# ewal.net
KiCad netlist of a schematic drawn in EAGLE
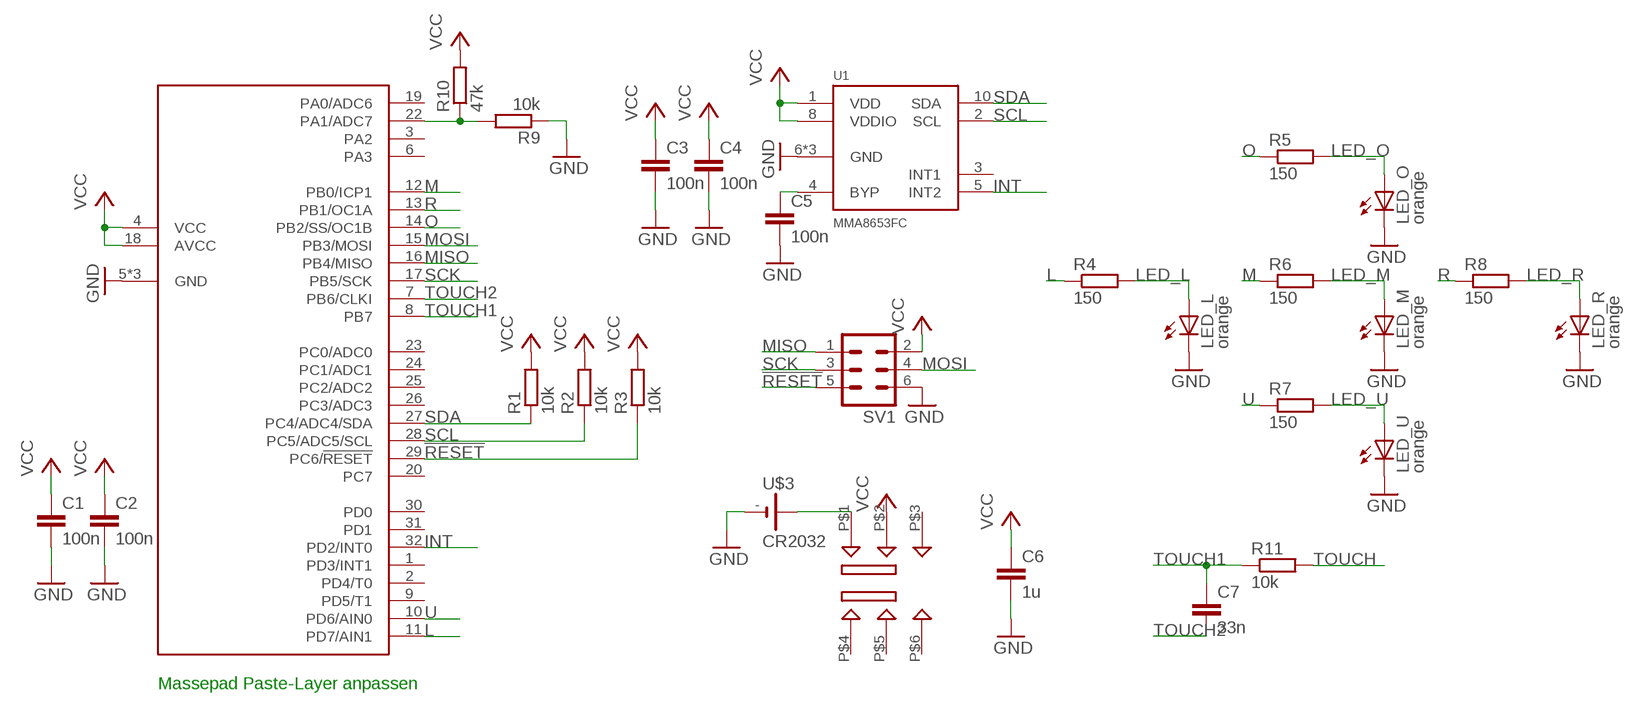
[diagram p0: schematic, sheet 1]

(export (version "E")
  (design (tool "Eeschema 10.0.6"))
  (components
    (comp (ref "C1")
      (value "100n")
      (footprint "eagle-import:C0603")
      (libsource (lib "eagle-import") (part "C-EUC0603"))
    )
    (comp (ref "C2")
      (value "100n")
      (footprint "eagle-import:C0603")
      (libsource (lib "eagle-import") (part "C-EUC0603"))
    )
    (comp (ref "C3")
      (value "100n")
      (footprint "eagle-import:C0603")
      (libsource (lib "eagle-import") (part "C-EUC0603"))
    )
    (comp (ref "C4")
      (value "100n")
      (footprint "eagle-import:C0603")
      (libsource (lib "eagle-import") (part "C-EUC0603"))
    )
    (comp (ref "C5")
      (value "100n")
      (footprint "eagle-import:C0603")
      (libsource (lib "eagle-import") (part "C-EUC0603"))
    )
    (comp (ref "C6")
      (value "1u")
      (footprint "eagle-import:C0805")
      (libsource (lib "eagle-import") (part "C-EUC0805"))
    )
    (comp (ref "C7")
      (value "33n")
      (footprint "eagle-import:C0603")
      (libsource (lib "eagle-import") (part "C-EUC0603"))
    )
    (comp (ref "LED_L")
      (value "orange")
      (footprint "eagle-import:CHIP-LED0603")
      (libsource (lib "eagle-import") (part "LEDCHIP-LED0603"))
    )
    (comp (ref "LED_M")
      (value "orange")
      (footprint "eagle-import:CHIP-LED0603")
      (libsource (lib "eagle-import") (part "LEDCHIP-LED0603"))
    )
    (comp (ref "LED_O")
      (value "orange")
      (footprint "eagle-import:CHIP-LED0603")
      (libsource (lib "eagle-import") (part "LEDCHIP-LED0603"))
    )
    (comp (ref "LED_R")
      (value "orange")
      (footprint "eagle-import:CHIP-LED0603")
      (libsource (lib "eagle-import") (part "LEDCHIP-LED0603"))
    )
    (comp (ref "LED_U")
      (value "orange")
      (footprint "eagle-import:CHIP-LED0603")
      (libsource (lib "eagle-import") (part "LEDCHIP-LED0603"))
    )
    (comp (ref "R1")
      (value "10k")
      (footprint "eagle-import:R0603")
      (libsource (lib "eagle-import") (part "R-EU_R0603"))
    )
    (comp (ref "R2")
      (value "10k")
      (footprint "eagle-import:R0603")
      (libsource (lib "eagle-import") (part "R-EU_R0603"))
    )
    (comp (ref "R3")
      (value "10k")
      (footprint "eagle-import:R0603")
      (libsource (lib "eagle-import") (part "R-EU_R0603"))
    )
    (comp (ref "R4")
      (value "150")
      (footprint "eagle-import:R0603")
      (libsource (lib "eagle-import") (part "R-EU_R0603"))
    )
    (comp (ref "R5")
      (value "150")
      (footprint "eagle-import:R0603")
      (libsource (lib "eagle-import") (part "R-EU_R0603"))
    )
    (comp (ref "R6")
      (value "150")
      (footprint "eagle-import:R0603")
      (libsource (lib "eagle-import") (part "R-EU_R0603"))
    )
    (comp (ref "R7")
      (value "150")
      (footprint "eagle-import:R0603")
      (libsource (lib "eagle-import") (part "R-EU_R0603"))
    )
    (comp (ref "R8")
      (value "150")
      (footprint "eagle-import:R0603")
      (libsource (lib "eagle-import") (part "R-EU_R0603"))
    )
    (comp (ref "R9")
      (value "10k")
      (footprint "eagle-import:R0603")
      (libsource (lib "eagle-import") (part "R-EU_R0603"))
    )
    (comp (ref "R10")
      (value "47k")
      (footprint "eagle-import:R0603")
      (libsource (lib "eagle-import") (part "R-EU_R0603"))
    )
    (comp (ref "R11")
      (value "10k")
      (footprint "eagle-import:R0603")
      (libsource (lib "eagle-import") (part "R-EU_R0603"))
    )
    (comp (ref "SV1")
      (value "MA03-2")
      (footprint "eagle-import:MA03-2")
      (libsource (lib "eagle-import") (part "MA03-2"))
    )
    (comp (ref "U$3")
      (value "CR2032")
      (footprint "eagle-import:BK-912")
      (libsource (lib "eagle-import") (part "CR2032"))
    )
    (comp (ref "U$4")
      (value "JS202011SCQN")
      (footprint "eagle-import:JS202011SCQN")
      (libsource (lib "eagle-import") (part "JS202011SCQN"))
    )
    (comp (ref "U1")
      (value "MMA8653FC")
      (footprint "eagle-import:2X2_DFN_LONGPADS")
      (libsource (lib "eagle-import") (part "MMA8653FC"))
    )
    (comp (ref "U2")
      (value "ATTINY48")
      (footprint "eagle-import:MLF32-TH")
      (libsource (lib "eagle-import") (part "ATTINY48"))
    )
  )
  (nets
    (net (code "1") (name "/INT") (class "Default")
      (node (ref "U1") (pin "5") (pinfunction "INT2_5") (pintype "output"))
      (node (ref "U2") (pin "32") (pinfunction "PD2/INT0_32") (pintype "bidirectional"))
    )
    (net (code "2") (name "/L") (class "Default")
      (node (ref "R4") (pin "1") (pinfunction "1_1") (pintype "passive"))
      (node (ref "U2") (pin "11") (pinfunction "PD7/AIN1_11") (pintype "bidirectional"))
    )
    (net (code "3") (name "/LED_L") (class "Default")
      (node (ref "LED_L") (pin "A") (pinfunction "A_A") (pintype "passive"))
      (node (ref "R4") (pin "2") (pinfunction "2_2") (pintype "passive"))
    )
    (net (code "4") (name "/LED_M") (class "Default")
      (node (ref "LED_M") (pin "A") (pinfunction "A_A") (pintype "passive"))
      (node (ref "R6") (pin "2") (pinfunction "2_2") (pintype "passive"))
    )
    (net (code "5") (name "/LED_O") (class "Default")
      (node (ref "LED_O") (pin "A") (pinfunction "A_A") (pintype "passive"))
      (node (ref "R5") (pin "2") (pinfunction "2_2") (pintype "passive"))
    )
    (net (code "6") (name "/LED_R") (class "Default")
      (node (ref "LED_R") (pin "A") (pinfunction "A_A") (pintype "passive"))
      (node (ref "R8") (pin "2") (pinfunction "2_2") (pintype "passive"))
    )
    (net (code "7") (name "/LED_U") (class "Default")
      (node (ref "LED_U") (pin "A") (pinfunction "A_A") (pintype "passive"))
      (node (ref "R7") (pin "2") (pinfunction "2_2") (pintype "passive"))
    )
    (net (code "8") (name "/M") (class "Default")
      (node (ref "R6") (pin "1") (pinfunction "1_1") (pintype "passive"))
      (node (ref "U2") (pin "12") (pinfunction "PB0/ICP1_12") (pintype "bidirectional"))
    )
    (net (code "9") (name "/MISO") (class "Default")
      (node (ref "SV1") (pin "1") (pinfunction "1_1") (pintype "passive"))
      (node (ref "U2") (pin "16") (pinfunction "PB4/MISO_16") (pintype "bidirectional"))
    )
    (net (code "10") (name "/MOSI") (class "Default")
      (node (ref "SV1") (pin "4") (pinfunction "4_4") (pintype "passive"))
      (node (ref "U2") (pin "15") (pinfunction "PB3/MOSI_15") (pintype "bidirectional"))
    )
    (net (code "11") (name "/O") (class "Default")
      (node (ref "R5") (pin "1") (pinfunction "1_1") (pintype "passive"))
      (node (ref "U2") (pin "14") (pinfunction "PB2/SS/OC1B_14") (pintype "bidirectional"))
    )
    (net (code "12") (name "/R") (class "Default")
      (node (ref "R8") (pin "1") (pinfunction "1_1") (pintype "passive"))
      (node (ref "U2") (pin "13") (pinfunction "PB1/OC1A_13") (pintype "bidirectional"))
    )
    (net (code "13") (name "/SCK") (class "Default")
      (node (ref "SV1") (pin "3") (pinfunction "3_3") (pintype "passive"))
      (node (ref "U2") (pin "17") (pinfunction "PB5/SCK_17") (pintype "bidirectional"))
    )
    (net (code "14") (name "/SCL") (class "Default")
      (node (ref "R2") (pin "1") (pinfunction "1_1") (pintype "passive"))
      (node (ref "U1") (pin "2") (pinfunction "SCL_2") (pintype "bidirectional"))
      (node (ref "U2") (pin "28") (pinfunction "PC5/ADC5/SCL_28") (pintype "bidirectional"))
    )
    (net (code "15") (name "/SDA") (class "Default")
      (node (ref "R1") (pin "1") (pinfunction "1_1") (pintype "passive"))
      (node (ref "U1") (pin "10") (pinfunction "SDA_10") (pintype "bidirectional"))
      (node (ref "U2") (pin "27") (pinfunction "PC4/ADC4/SDA_27") (pintype "bidirectional"))
    )
    (net (code "16") (name "/TOUCH") (class "Default")
      (node (ref "R11") (pin "2") (pinfunction "2_2") (pintype "passive"))
    )
    (net (code "17") (name "/TOUCH1") (class "Default")
      (node (ref "C7") (pin "1") (pinfunction "1_1") (pintype "passive"))
      (node (ref "R11") (pin "1") (pinfunction "1_1") (pintype "passive"))
      (node (ref "U2") (pin "8") (pinfunction "PB7_8") (pintype "bidirectional"))
    )
    (net (code "18") (name "/TOUCH2") (class "Default")
      (node (ref "C7") (pin "2") (pinfunction "2_2") (pintype "passive"))
      (node (ref "U2") (pin "7") (pinfunction "PB6/CLKI_7") (pintype "bidirectional"))
    )
    (net (code "19") (name "/U") (class "Default")
      (node (ref "R7") (pin "1") (pinfunction "1_1") (pintype "passive"))
      (node (ref "U2") (pin "10") (pinfunction "PD6/AIN0_10") (pintype "bidirectional"))
    )
    (net (code "20") (name "/~{RESET}") (class "Default")
      (node (ref "R3") (pin "1") (pinfunction "1_1") (pintype "passive"))
      (node (ref "SV1") (pin "5") (pinfunction "5_5") (pintype "passive"))
      (node (ref "U2") (pin "29") (pinfunction "PC6/~{RESET}_29") (pintype "bidirectional"))
    )
    (net (code "21") (name "GND") (class "Default")
      (node (ref "C1") (pin "2") (pinfunction "2_2") (pintype "passive"))
      (node (ref "C2") (pin "2") (pinfunction "2_2") (pintype "passive"))
      (node (ref "C3") (pin "2") (pinfunction "2_2") (pintype "passive"))
      (node (ref "C4") (pin "2") (pinfunction "2_2") (pintype "passive"))
      (node (ref "C5") (pin "2") (pinfunction "2_2") (pintype "passive"))
      (node (ref "C6") (pin "2") (pinfunction "2_2") (pintype "passive"))
      (node (ref "LED_L") (pin "C") (pinfunction "C_C") (pintype "passive"))
      (node (ref "LED_M") (pin "C") (pinfunction "C_C") (pintype "passive"))
      (node (ref "LED_O") (pin "C") (pinfunction "C_C") (pintype "passive"))
      (node (ref "LED_R") (pin "C") (pinfunction "C_C") (pintype "passive"))
      (node (ref "LED_U") (pin "C") (pinfunction "C_C") (pintype "passive"))
      (node (ref "R9") (pin "1") (pinfunction "1_1") (pintype "passive"))
      (node (ref "SV1") (pin "6") (pinfunction "6_6") (pintype "passive"))
      (node (ref "U$3") (pin "-") (pinfunction "-_-") (pintype "passive"))
      (node (ref "U1") (pin "6") (pinfunction "GND_6") (pintype "bidirectional"))
      (node (ref "U1") (pin "7") (pinfunction "GND_7") (pintype "bidirectional"))
      (node (ref "U1") (pin "9") (pinfunction "GND_9") (pintype "bidirectional"))
      (node (ref "U2") (pin "21") (pinfunction "GND_21") (pintype "bidirectional"))
      (node (ref "U2") (pin "5") (pinfunction "GND_5") (pintype "bidirectional"))
      (node (ref "U2") (pin "TH") (pinfunction "GND_TH") (pintype "bidirectional"))
    )
    (net (code "22") (name "Net-(U$3-+-Pad+@1)") (class "Default")
      (node (ref "U$3") (pin "+@1") (pinfunction "+_+@1") (pintype "passive"))
      (node (ref "U$3") (pin "+@2") (pinfunction "+_+@2") (pintype "passive"))
      (node (ref "U$4") (pin "P$1") (pinfunction "P$1_P$1") (pintype "bidirectional"))
    )
    (net (code "23") (name "Net-(U1-BYP)") (class "Default")
      (node (ref "C5") (pin "1") (pinfunction "1_1") (pintype "passive"))
      (node (ref "U1") (pin "4") (pinfunction "BYP_4") (pintype "passive"))
    )
    (net (code "24") (name "Net-(U2-PA1{slash}ADC7)") (class "Default")
      (node (ref "R10") (pin "1") (pinfunction "1_1") (pintype "passive"))
      (node (ref "R9") (pin "2") (pinfunction "2_2") (pintype "passive"))
      (node (ref "U2") (pin "22") (pinfunction "PA1/ADC7_22") (pintype "bidirectional"))
    )
    (net (code "25") (name "VCC") (class "Default")
      (node (ref "C1") (pin "1") (pinfunction "1_1") (pintype "passive"))
      (node (ref "C2") (pin "1") (pinfunction "1_1") (pintype "passive"))
      (node (ref "C3") (pin "1") (pinfunction "1_1") (pintype "passive"))
      (node (ref "C4") (pin "1") (pinfunction "1_1") (pintype "passive"))
      (node (ref "C6") (pin "1") (pinfunction "1_1") (pintype "passive"))
      (node (ref "R1") (pin "2") (pinfunction "2_2") (pintype "passive"))
      (node (ref "R10") (pin "2") (pinfunction "2_2") (pintype "passive"))
      (node (ref "R2") (pin "2") (pinfunction "2_2") (pintype "passive"))
      (node (ref "R3") (pin "2") (pinfunction "2_2") (pintype "passive"))
      (node (ref "SV1") (pin "2") (pinfunction "2_2") (pintype "passive"))
      (node (ref "U$4") (pin "P$2") (pinfunction "P$2_P$2") (pintype "bidirectional"))
      (node (ref "U1") (pin "1") (pinfunction "VDD_1") (pintype "power_in"))
      (node (ref "U1") (pin "8") (pinfunction "VDDIO_8") (pintype "power_in"))
      (node (ref "U2") (pin "18") (pinfunction "AVCC_18") (pintype "bidirectional"))
      (node (ref "U2") (pin "4") (pinfunction "VCC_4") (pintype "bidirectional"))
    )
    (net (code "26") (name "unconnected-(U$4-PadP$3)") (class "Default")
      (node (ref "U$4") (pin "P$3") (pinfunction "P$3_P$3") (pintype "bidirectional"))
    )
    (net (code "27") (name "unconnected-(U$4-PadP$4)") (class "Default")
      (node (ref "U$4") (pin "P$4") (pinfunction "P$4_P$4") (pintype "bidirectional"))
    )
    (net (code "28") (name "unconnected-(U$4-PadP$5)") (class "Default")
      (node (ref "U$4") (pin "P$5") (pinfunction "P$5_P$5") (pintype "bidirectional"))
    )
    (net (code "29") (name "unconnected-(U$4-PadP$6)") (class "Default")
      (node (ref "U$4") (pin "P$6") (pinfunction "P$6_P$6") (pintype "bidirectional"))
    )
    (net (code "30") (name "unconnected-(U1-INT1-Pad3)") (class "Default")
      (node (ref "U1") (pin "3") (pinfunction "INT1_3") (pintype "output"))
    )
    (net (code "31") (name "unconnected-(U2-PA0{slash}ADC6-Pad19)") (class "Default")
      (node (ref "U2") (pin "19") (pinfunction "PA0/ADC6_19") (pintype "bidirectional"))
    )
    (net (code "32") (name "unconnected-(U2-PA2-Pad3)") (class "Default")
      (node (ref "U2") (pin "3") (pinfunction "PA2_3") (pintype "bidirectional"))
    )
    (net (code "33") (name "unconnected-(U2-PA3-Pad6)") (class "Default")
      (node (ref "U2") (pin "6") (pinfunction "PA3_6") (pintype "bidirectional"))
    )
    (net (code "34") (name "unconnected-(U2-PC0{slash}ADC0-Pad23)") (class "Default")
      (node (ref "U2") (pin "23") (pinfunction "PC0/ADC0_23") (pintype "bidirectional"))
    )
    (net (code "35") (name "unconnected-(U2-PC1{slash}ADC1-Pad24)") (class "Default")
      (node (ref "U2") (pin "24") (pinfunction "PC1/ADC1_24") (pintype "bidirectional"))
    )
    (net (code "36") (name "unconnected-(U2-PC2{slash}ADC2-Pad25)") (class "Default")
      (node (ref "U2") (pin "25") (pinfunction "PC2/ADC2_25") (pintype "bidirectional"))
    )
    (net (code "37") (name "unconnected-(U2-PC3{slash}ADC3-Pad26)") (class "Default")
      (node (ref "U2") (pin "26") (pinfunction "PC3/ADC3_26") (pintype "bidirectional"))
    )
    (net (code "38") (name "unconnected-(U2-PC7-Pad20)") (class "Default")
      (node (ref "U2") (pin "20") (pinfunction "PC7_20") (pintype "bidirectional"))
    )
    (net (code "39") (name "unconnected-(U2-PD0-Pad30)") (class "Default")
      (node (ref "U2") (pin "30") (pinfunction "PD0_30") (pintype "bidirectional"))
    )
    (net (code "40") (name "unconnected-(U2-PD1-Pad31)") (class "Default")
      (node (ref "U2") (pin "31") (pinfunction "PD1_31") (pintype "bidirectional"))
    )
    (net (code "41") (name "unconnected-(U2-PD3{slash}INT1-Pad1)") (class "Default")
      (node (ref "U2") (pin "1") (pinfunction "PD3/INT1_1") (pintype "bidirectional"))
    )
    (net (code "42") (name "unconnected-(U2-PD4{slash}T0-Pad2)") (class "Default")
      (node (ref "U2") (pin "2") (pinfunction "PD4/T0_2") (pintype "bidirectional"))
    )
    (net (code "43") (name "unconnected-(U2-PD5{slash}T1-Pad9)") (class "Default")
      (node (ref "U2") (pin "9") (pinfunction "PD5/T1_9") (pintype "bidirectional"))
    )
  )
)
